# VREG_AOZ1021AI_3V3_3A.net
KiCad netlist of a schematic drawn in Altium Designer
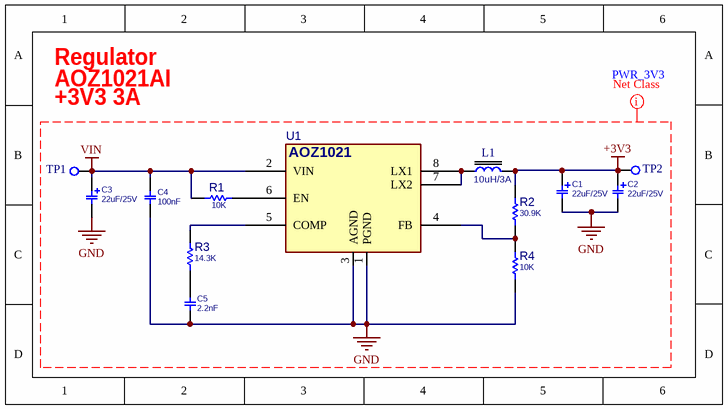
[diagram p0: VREG AOZ1021AI +3V3 3A.SchDoc]

(export (version "E")
  (design (tool "Eeschema 10.0.6"))
  (components
    (comp (ref "C1")
      (value "22uF/25V")
      (footprint "C_TN_3216")
      (description "CAP, SMD, TAN")
      (libsource (lib "Passive") (part "CAP_SMD_TAN"))
    )
    (comp (ref "C2")
      (value "22uF/25V")
      (footprint "C_TN_3216")
      (description "CAP, SMD, TAN")
      (libsource (lib "Passive") (part "CAP_SMD_TAN"))
    )
    (comp (ref "C3")
      (value "22uF/25V")
      (footprint "C_TN_3216")
      (description "CAP, SMD, TAN")
      (libsource (lib "Passive") (part "CAP_SMD_TAN"))
    )
    (comp (ref "C4")
      (value "100nF")
      (footprint "C0603S")
      (description "CAP, SMD, MLCC")
      (fields (field (name "MANF_P#") "MANF_PART#") (field (name "MANF") "Murata"))
      (libsource (lib "Passive") (part "CAP_SMD_MLCC"))
    )
    (comp (ref "C5")
      (value "2.2nF")
      (footprint "C0603S")
      (description "CAP, SMD, MLCC")
      (fields (field (name "MANF_P#") "MANF_PART#") (field (name "MANF") "Murata"))
      (libsource (lib "Passive") (part "CAP_SMD_MLCC"))
    )
    (comp (ref "L1")
      (value "10uH/3A")
      (footprint "L_8")
      (description "IND, PWR, SMD")
      (libsource (lib "Passive") (part "INDPWR_SMD"))
    )
    (comp (ref "R1")
      (value "10K")
      (footprint "R0603S")
      (description "RES, SMD")
      (fields (field (name "MANF_P#") "RK73H1ETTP4701F") (field (name "MANF") "KOA SPEER"))
      (libsource (lib "Passive") (part "RES_SMD"))
    )
    (comp (ref "R2")
      (value "30.9K")
      (footprint "R0603S")
      (description "RES, SMD")
      (fields (field (name "MANF_P#") "RK73H1ETTP4701F") (field (name "MANF") "KOA SPEER"))
      (libsource (lib "Passive") (part "RES_SMD"))
    )
    (comp (ref "R3")
      (value "14.3K")
      (footprint "R0603S")
      (description "RES, SMD")
      (fields (field (name "MANF_P#") "RK73H1ETTP4701F") (field (name "MANF") "KOA SPEER"))
      (libsource (lib "Passive") (part "RES_SMD"))
    )
    (comp (ref "R4")
      (value "10K")
      (footprint "R0603S")
      (description "RES, SMD")
      (fields (field (name "MANF_P#") "RK73H1ETTP4701F") (field (name "MANF") "KOA SPEER"))
      (libsource (lib "Passive") (part "RES_SMD"))
    )
    (comp (ref "TP1")
      (value "Test Point")
      (footprint "TPSMD_C1")
      (libsource (lib "PW Components") (part "Test Point"))
    )
    (comp (ref "TP2")
      (value "Test Point")
      (footprint "TPSMD_C1")
      (libsource (lib "PW Components") (part "Test Point"))
    )
    (comp (ref "U1")
      (value "AOZ1021AI")
      (footprint "SO_8")
      (description "REG, Switching, Buck, 3A, ADJ, 500KHz, 4.5~16VIN, SO-8")
      (fields (field (name "MANF") "AOSMD"))
      (libsource (lib "PW Components") (part "VREG_AOZ1021AI_SO8"))
    )
  )
  (nets
    (net (code "1") (name "+3V3") (class "Default")
      (node (ref "C1") (pin "1") (pinfunction "1_1") (pintype "passive"))
      (node (ref "C2") (pin "1") (pinfunction "1_1") (pintype "passive"))
      (node (ref "L1") (pin "2") (pinfunction "2_2") (pintype "passive"))
      (node (ref "R2") (pin "1") (pinfunction "1_1") (pintype "passive"))
      (node (ref "TP2") (pin "1") (pinfunction "TP_1") (pintype "passive"))
    )
    (net (code "2") (name "GND") (class "Default")
      (node (ref "C1") (pin "2") (pinfunction "2_2") (pintype "passive"))
      (node (ref "C2") (pin "2") (pinfunction "2_2") (pintype "passive"))
      (node (ref "C3") (pin "2") (pinfunction "2_2") (pintype "passive"))
      (node (ref "C4") (pin "1") (pinfunction "1_1") (pintype "passive"))
      (node (ref "C5") (pin "1") (pinfunction "1_1") (pintype "passive"))
      (node (ref "R4") (pin "2") (pinfunction "2_2") (pintype "passive"))
      (node (ref "U1") (pin "1") (pinfunction "PGND_1") (pintype "power_in"))
      (node (ref "U1") (pin "3") (pinfunction "AGND_3") (pintype "power_in"))
    )
    (net (code "3") (name "Net-(C5-Pad2)") (class "Default")
      (node (ref "C5") (pin "2") (pinfunction "2_2") (pintype "passive"))
      (node (ref "R3") (pin "2") (pinfunction "2_2") (pintype "passive"))
    )
    (net (code "4") (name "Net-(U1-COMP)") (class "Default")
      (node (ref "R3") (pin "1") (pinfunction "1_1") (pintype "passive"))
      (node (ref "U1") (pin "5") (pinfunction "COMP_5") (pintype "passive"))
    )
    (net (code "5") (name "Net-(U1-EN)") (class "Default")
      (node (ref "R1") (pin "1") (pinfunction "1_1") (pintype "passive"))
      (node (ref "U1") (pin "6") (pinfunction "EN_6") (pintype "passive"))
    )
    (net (code "6") (name "Net-(U1-FB)") (class "Default")
      (node (ref "R2") (pin "2") (pinfunction "2_2") (pintype "passive"))
      (node (ref "R4") (pin "1") (pinfunction "1_1") (pintype "passive"))
      (node (ref "U1") (pin "4") (pinfunction "FB_4") (pintype "passive"))
    )
    (net (code "7") (name "Net-(U1-LX1)") (class "Default")
      (node (ref "L1") (pin "1") (pinfunction "1_1") (pintype "passive"))
      (node (ref "U1") (pin "7") (pinfunction "LX2_7") (pintype "passive"))
      (node (ref "U1") (pin "8") (pinfunction "LX1_8") (pintype "passive"))
    )
    (net (code "8") (name "VIN") (class "Default")
      (node (ref "C3") (pin "1") (pinfunction "1_1") (pintype "passive"))
      (node (ref "C4") (pin "2") (pinfunction "2_2") (pintype "passive"))
      (node (ref "R1") (pin "2") (pinfunction "2_2") (pintype "passive"))
      (node (ref "TP1") (pin "1") (pinfunction "TP_1") (pintype "passive"))
      (node (ref "U1") (pin "2") (pinfunction "VIN_2") (pintype "power_in"))
    )
  )
)
